# mavroOBD.net
KiCad netlist of a schematic drawn in EAGLE
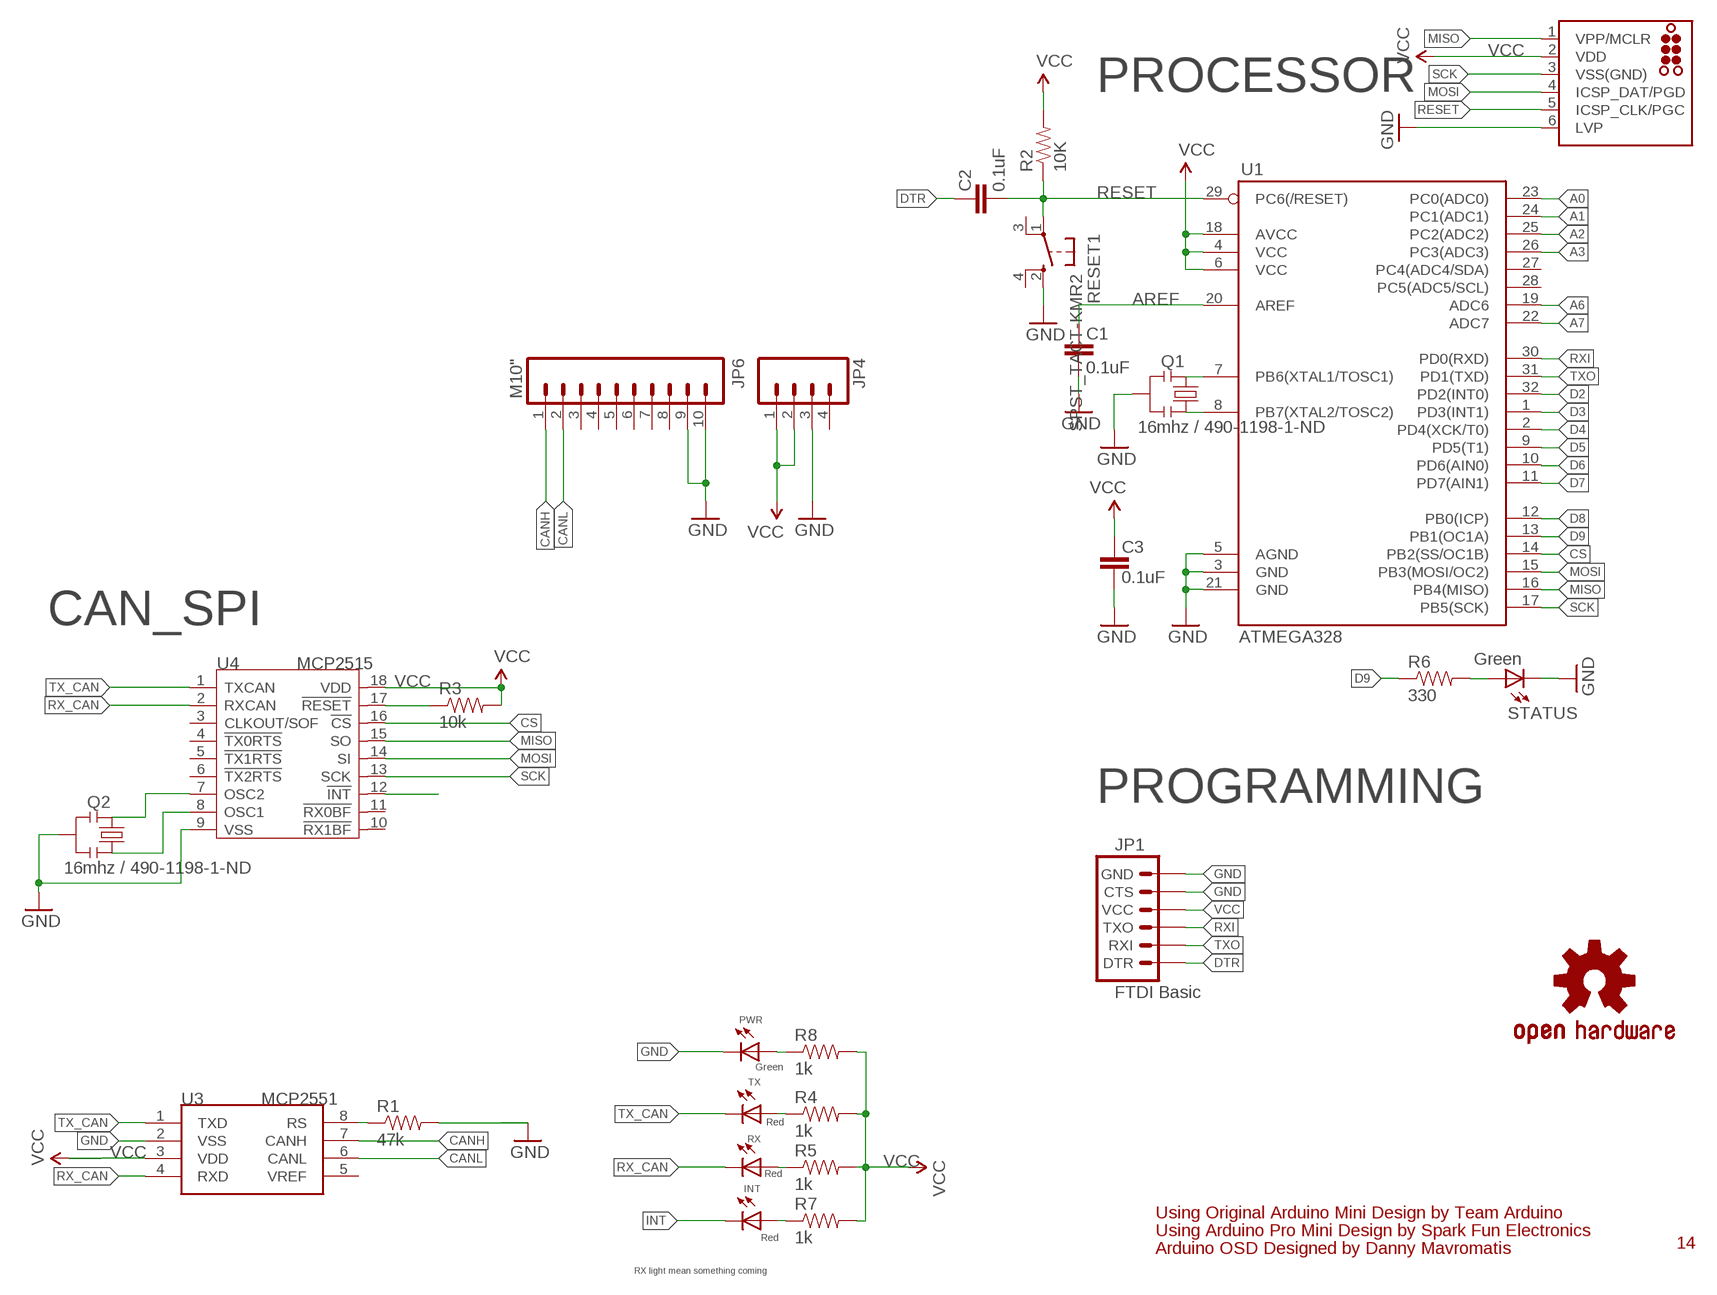
[diagram p0: schematic, sheet 1]

(export (version "E")
  (design (tool "Eeschema 10.0.6"))
  (components
    (comp (ref "C1")
      (value "0.1uF")
      (footprint "eagle-import:0603-CAP")
      (libsource (lib "eagle-import") (part "CAP0603-CAP"))
    )
    (comp (ref "C2")
      (value "0.1uF")
      (footprint "eagle-import:0603-CAP")
      (libsource (lib "eagle-import") (part "CAP0603-CAP"))
    )
    (comp (ref "C3")
      (value "0.1uF")
      (footprint "eagle-import:0603-CAP")
      (libsource (lib "eagle-import") (part "CAP0603-CAP"))
    )
    (comp (ref "INT")
      (value "Red")
      (footprint "eagle-import:0603-LED-ALT1")
      (libsource (lib "eagle-import") (part "LED"))
    )
    (comp (ref "J1")
      (value "TC2030-MCP-NL")
      (footprint "eagle-import:TC2030-MCP-NL")
      (libsource (lib "eagle-import") (part "TC2030-MCP-NL"))
    )
    (comp (ref "JP1")
      (value "FTDI Basic")
      (footprint "eagle-import:1X06")
      (libsource (lib "eagle-import") (part "ARDUINO_SERIAL_PROGRAMPTH"))
    )
    (comp (ref "JP4")
      (value "M04PTH")
      (footprint "eagle-import:1X04")
      (libsource (lib "eagle-import") (part "M04PTH"))
    )
    (comp (ref "JP6")
      (value "M10\"")
      (footprint "eagle-import:1X10")
      (libsource (lib "eagle-import") (part "M10{dblquote}"))
    )
    (comp (ref "PWR")
      (value "Green")
      (footprint "eagle-import:0603-LED-ALT1")
      (libsource (lib "eagle-import") (part "LED"))
    )
    (comp (ref "Q1")
      (value "16mhz / 490-1198-1-ND")
      (footprint "eagle-import:RESONATOR-SMD-1_1")
      (libsource (lib "eagle-import") (part "RESONATOR1{colon}1"))
    )
    (comp (ref "Q2")
      (value "16mhz / 490-1198-1-ND")
      (footprint "eagle-import:RESONATOR-SMD-1_1")
      (libsource (lib "eagle-import") (part "RESONATOR1{colon}1"))
    )
    (comp (ref "R1")
      (value "47k")
      (footprint "eagle-import:0603-RES")
      (libsource (lib "eagle-import") (part "SparkFun-Passives_RESISTOR0603-RES"))
    )
    (comp (ref "R2")
      (value "10K")
      (footprint "eagle-import:0603-RES")
      (libsource (lib "eagle-import") (part "RESISTOR0603-RES"))
    )
    (comp (ref "R3")
      (value "10k")
      (footprint "eagle-import:0603-RES")
      (libsource (lib "eagle-import") (part "SparkFun-Passives_RESISTOR0603-RES"))
    )
    (comp (ref "R4")
      (value "1k")
      (footprint "eagle-import:0603-RES")
      (libsource (lib "eagle-import") (part "SparkFun-Passives_RESISTOR0603-RES"))
    )
    (comp (ref "R5")
      (value "1k")
      (footprint "eagle-import:0603-RES")
      (libsource (lib "eagle-import") (part "SparkFun-Passives_RESISTOR0603-RES"))
    )
    (comp (ref "R6")
      (value "330")
      (footprint "eagle-import:0603-RES")
      (libsource (lib "eagle-import") (part "RESISTOR0603-RES"))
    )
    (comp (ref "R7")
      (value "1k")
      (footprint "eagle-import:0603-RES")
      (libsource (lib "eagle-import") (part "SparkFun-Passives_RESISTOR0603-RES"))
    )
    (comp (ref "R8")
      (value "1k")
      (footprint "eagle-import:0603-RES")
      (libsource (lib "eagle-import") (part "SparkFun-Passives_RESISTOR0603-RES"))
    )
    (comp (ref "RESET1")
      (value "SPST_TACT-KMR2")
      (footprint "eagle-import:KMR2")
      (libsource (lib "eagle-import") (part "SPST_TACT-KMR2"))
    )
    (comp (ref "RX")
      (value "Red")
      (footprint "eagle-import:0603-LED-ALT1")
      (libsource (lib "eagle-import") (part "LED"))
    )
    (comp (ref "STATUS")
      (value "Green")
      (footprint "eagle-import:0603-LED-ALT1")
      (libsource (lib "eagle-import") (part "LED"))
    )
    (comp (ref "TX")
      (value "Red")
      (footprint "eagle-import:0603-LED-ALT1")
      (libsource (lib "eagle-import") (part "LED"))
    )
    (comp (ref "U$3")
      (value "OSHW-LOGOS")
      (footprint "eagle-import:OSHW-LOGO-S")
      (libsource (lib "eagle-import") (part "OSHW-LOGOS"))
    )
    (comp (ref "U1")
      (value "ATMEGA328")
      (footprint "eagle-import:TQFP32-08")
      (libsource (lib "eagle-import") (part "ATMEGA168"))
    )
    (comp (ref "U3")
      (value "MCP2551")
      (footprint "eagle-import:SOIC8-6.0")
      (libsource (lib "eagle-import") (part "MCP2551-SOIC8"))
    )
    (comp (ref "U4")
      (value "MCP2515")
      (footprint "eagle-import:SOIC18")
      (libsource (lib "eagle-import") (part "MCP2515-SOIC18"))
    )
  )
  (nets
    (net (code "1") (name "/AREF") (class "Default")
      (node (ref "C1") (pin "2") (pinfunction "2_2") (pintype "passive"))
      (node (ref "U1") (pin "20") (pinfunction "AREF_20") (pintype "bidirectional"))
    )
    (net (code "2") (name "A0") (class "Default")
      (node (ref "U1") (pin "23") (pinfunction "PC0(ADC0)_23") (pintype "bidirectional"))
    )
    (net (code "3") (name "A1") (class "Default")
      (node (ref "U1") (pin "24") (pinfunction "PC1(ADC1)_24") (pintype "bidirectional"))
    )
    (net (code "4") (name "A2") (class "Default")
      (node (ref "U1") (pin "25") (pinfunction "PC2(ADC2)_25") (pintype "bidirectional"))
    )
    (net (code "5") (name "A3") (class "Default")
      (node (ref "U1") (pin "26") (pinfunction "PC3(ADC3)_26") (pintype "bidirectional"))
    )
    (net (code "6") (name "A6") (class "Default")
      (node (ref "U1") (pin "19") (pinfunction "ADC6_19") (pintype "bidirectional"))
    )
    (net (code "7") (name "A7") (class "Default")
      (node (ref "U1") (pin "22") (pinfunction "ADC7_22") (pintype "bidirectional"))
    )
    (net (code "8") (name "CANH") (class "Default")
      (node (ref "JP6") (pin "1") (pinfunction "1_1") (pintype "passive"))
      (node (ref "U3") (pin "7") (pinfunction "CANH_7") (pintype "bidirectional"))
    )
    (net (code "9") (name "CANL") (class "Default")
      (node (ref "JP6") (pin "2") (pinfunction "2_2") (pintype "passive"))
      (node (ref "U3") (pin "6") (pinfunction "CANL_6") (pintype "bidirectional"))
    )
    (net (code "10") (name "CS") (class "Default")
      (node (ref "U1") (pin "14") (pinfunction "PB2(SS/OC1B)_14") (pintype "bidirectional"))
      (node (ref "U4") (pin "16") (pinfunction "~{CS}_16") (pintype "input"))
    )
    (net (code "11") (name "D2") (class "Default")
      (node (ref "U1") (pin "32") (pinfunction "PD2(INT0)_32") (pintype "bidirectional"))
    )
    (net (code "12") (name "D3") (class "Default")
      (node (ref "U1") (pin "1") (pinfunction "PD3(INT1)_1") (pintype "bidirectional"))
    )
    (net (code "13") (name "D4") (class "Default")
      (node (ref "U1") (pin "2") (pinfunction "PD4(XCK/T0)_2") (pintype "bidirectional"))
    )
    (net (code "14") (name "D5") (class "Default")
      (node (ref "U1") (pin "9") (pinfunction "PD5(T1)_9") (pintype "bidirectional"))
    )
    (net (code "15") (name "D6") (class "Default")
      (node (ref "U1") (pin "10") (pinfunction "PD6(AIN0)_10") (pintype "bidirectional"))
    )
    (net (code "16") (name "D7") (class "Default")
      (node (ref "U1") (pin "11") (pinfunction "PD7(AIN1)_11") (pintype "bidirectional"))
    )
    (net (code "17") (name "D8") (class "Default")
      (node (ref "U1") (pin "12") (pinfunction "PB0(ICP)_12") (pintype "bidirectional"))
    )
    (net (code "18") (name "D9") (class "Default")
      (node (ref "R6") (pin "1") (pinfunction "1_1") (pintype "passive"))
      (node (ref "U1") (pin "13") (pinfunction "PB1(OC1A)_13") (pintype "bidirectional"))
    )
    (net (code "19") (name "DTR") (class "Default")
      (node (ref "C2") (pin "2") (pinfunction "2_2") (pintype "passive"))
      (node (ref "JP1") (pin "1") (pinfunction "DTR_1") (pintype "passive"))
    )
    (net (code "20") (name "GND") (class "Default")
      (node (ref "C1") (pin "1") (pinfunction "1_1") (pintype "passive"))
      (node (ref "C3") (pin "1") (pinfunction "1_1") (pintype "passive"))
      (node (ref "J1") (pin "6") (pinfunction "LVP_6") (pintype "bidirectional"))
      (node (ref "JP1") (pin "5") (pinfunction "CTS_5") (pintype "passive"))
      (node (ref "JP1") (pin "6") (pinfunction "GND_6") (pintype "passive"))
      (node (ref "JP4") (pin "3") (pinfunction "3_3") (pintype "passive"))
      (node (ref "JP6") (pin "10") (pinfunction "10_10") (pintype "passive"))
      (node (ref "JP6") (pin "9") (pinfunction "9_9") (pintype "passive"))
      (node (ref "PWR") (pin "C") (pinfunction "C_C") (pintype "passive"))
      (node (ref "Q1") (pin "2") (pinfunction "2_2") (pintype "passive"))
      (node (ref "Q2") (pin "2") (pinfunction "2_2") (pintype "passive"))
      (node (ref "R1") (pin "2") (pinfunction "2_2") (pintype "passive"))
      (node (ref "RESET1") (pin "2") (pinfunction "S_2") (pintype "passive"))
      (node (ref "STATUS") (pin "C") (pinfunction "C_C") (pintype "passive"))
      (node (ref "U1") (pin "21") (pinfunction "GND_21") (pintype "bidirectional"))
      (node (ref "U1") (pin "3") (pinfunction "GND_3") (pintype "bidirectional"))
      (node (ref "U1") (pin "5") (pinfunction "AGND_5") (pintype "bidirectional"))
      (node (ref "U3") (pin "2") (pinfunction "VSS_2") (pintype "bidirectional"))
      (node (ref "U4") (pin "9") (pinfunction "VSS_9") (pintype "power_in"))
    )
    (net (code "21") (name "INT") (class "Default")
      (node (ref "INT") (pin "C") (pinfunction "C_C") (pintype "passive"))
      (node (ref "U4") (pin "12") (pinfunction "~{INT}_12") (pintype "output"))
    )
    (net (code "22") (name "MISO") (class "Default")
      (node (ref "J1") (pin "1") (pinfunction "VPP/MCLR_1") (pintype "passive"))
      (node (ref "U1") (pin "16") (pinfunction "PB4(MISO)_16") (pintype "bidirectional"))
      (node (ref "U4") (pin "15") (pinfunction "SO_15") (pintype "output"))
    )
    (net (code "23") (name "MOSI") (class "Default")
      (node (ref "J1") (pin "4") (pinfunction "ICSP_DAT/PGD_4") (pintype "bidirectional"))
      (node (ref "U1") (pin "15") (pinfunction "PB3(MOSI/OC2)_15") (pintype "bidirectional"))
      (node (ref "U4") (pin "14") (pinfunction "SI_14") (pintype "input"))
    )
    (net (code "24") (name "Net-(INT-PadA)") (class "Default")
      (node (ref "INT") (pin "A") (pinfunction "A_A") (pintype "passive"))
      (node (ref "R7") (pin "1") (pinfunction "1_1") (pintype "passive"))
    )
    (net (code "25") (name "Net-(PWR-PadA)") (class "Default")
      (node (ref "PWR") (pin "A") (pinfunction "A_A") (pintype "passive"))
      (node (ref "R8") (pin "1") (pinfunction "1_1") (pintype "passive"))
    )
    (net (code "26") (name "Net-(R4-Pad1)") (class "Default")
      (node (ref "R4") (pin "1") (pinfunction "1_1") (pintype "passive"))
      (node (ref "TX") (pin "A") (pinfunction "A_A") (pintype "passive"))
    )
    (net (code "27") (name "Net-(R5-Pad1)") (class "Default")
      (node (ref "R5") (pin "1") (pinfunction "1_1") (pintype "passive"))
      (node (ref "RX") (pin "A") (pinfunction "A_A") (pintype "passive"))
    )
    (net (code "28") (name "Net-(R6-Pad2)") (class "Default")
      (node (ref "R6") (pin "2") (pinfunction "2_2") (pintype "passive"))
      (node (ref "STATUS") (pin "A") (pinfunction "A_A") (pintype "passive"))
    )
    (net (code "29") (name "Net-(U1-PB6(XTAL1{slash}TOSC1))") (class "Default")
      (node (ref "Q1") (pin "1") (pinfunction "1_1") (pintype "passive"))
      (node (ref "U1") (pin "7") (pinfunction "PB6(XTAL1/TOSC1)_7") (pintype "bidirectional"))
    )
    (net (code "30") (name "Net-(U1-PB7(XTAL2{slash}TOSC2))") (class "Default")
      (node (ref "Q1") (pin "3") (pinfunction "3_3") (pintype "passive"))
      (node (ref "U1") (pin "8") (pinfunction "PB7(XTAL2/TOSC2)_8") (pintype "bidirectional"))
    )
    (net (code "31") (name "Net-(U3-RS)") (class "Default")
      (node (ref "R1") (pin "1") (pinfunction "1_1") (pintype "passive"))
      (node (ref "U3") (pin "8") (pinfunction "RS_8") (pintype "bidirectional"))
    )
    (net (code "32") (name "Net-(U4-OSC1)") (class "Default")
      (node (ref "Q2") (pin "3") (pinfunction "3_3") (pintype "passive"))
      (node (ref "U4") (pin "8") (pinfunction "OSC1_8") (pintype "input"))
    )
    (net (code "33") (name "Net-(U4-OSC2)") (class "Default")
      (node (ref "Q2") (pin "1") (pinfunction "1_1") (pintype "passive"))
      (node (ref "U4") (pin "7") (pinfunction "OSC2_7") (pintype "output"))
    )
    (net (code "34") (name "Net-(U4-~{RESET})") (class "Default")
      (node (ref "R3") (pin "1") (pinfunction "1_1") (pintype "passive"))
      (node (ref "U4") (pin "17") (pinfunction "~{RESET}_17") (pintype "input"))
    )
    (net (code "35") (name "RESET") (class "Default")
      (node (ref "C2") (pin "1") (pinfunction "1_1") (pintype "passive"))
      (node (ref "J1") (pin "5") (pinfunction "ICSP_CLK/PGC_5") (pintype "output"))
      (node (ref "R2") (pin "1") (pinfunction "1_1") (pintype "passive"))
      (node (ref "RESET1") (pin "1") (pinfunction "P_1") (pintype "passive"))
      (node (ref "U1") (pin "29") (pinfunction "PC6(/RESET)_29") (pintype "bidirectional"))
    )
    (net (code "36") (name "RXI") (class "Default")
      (node (ref "JP1") (pin "3") (pinfunction "TXO_3") (pintype "passive"))
      (node (ref "U1") (pin "30") (pinfunction "PD0(RXD)_30") (pintype "bidirectional"))
    )
    (net (code "37") (name "RX_CAN") (class "Default")
      (node (ref "RX") (pin "C") (pinfunction "C_C") (pintype "passive"))
      (node (ref "U3") (pin "4") (pinfunction "RXD_4") (pintype "bidirectional"))
      (node (ref "U4") (pin "2") (pinfunction "RXCAN_2") (pintype "input"))
    )
    (net (code "38") (name "SCK") (class "Default")
      (node (ref "J1") (pin "3") (pinfunction "VSS(GND)_3") (pintype "power_in"))
      (node (ref "U1") (pin "17") (pinfunction "PB5(SCK)_17") (pintype "bidirectional"))
      (node (ref "U4") (pin "13") (pinfunction "SCK_13") (pintype "input"))
    )
    (net (code "39") (name "TXO") (class "Default")
      (node (ref "JP1") (pin "2") (pinfunction "RXI_2") (pintype "passive"))
      (node (ref "U1") (pin "31") (pinfunction "PD1(TXD)_31") (pintype "bidirectional"))
    )
    (net (code "40") (name "TX_CAN") (class "Default")
      (node (ref "TX") (pin "C") (pinfunction "C_C") (pintype "passive"))
      (node (ref "U3") (pin "1") (pinfunction "TXD_1") (pintype "bidirectional"))
      (node (ref "U4") (pin "1") (pinfunction "TXCAN_1") (pintype "output"))
    )
    (net (code "41") (name "VCC") (class "Default")
      (node (ref "C3") (pin "2") (pinfunction "2_2") (pintype "passive"))
      (node (ref "J1") (pin "2") (pinfunction "VDD_2") (pintype "power_in"))
      (node (ref "JP1") (pin "4") (pinfunction "VCC_4") (pintype "passive"))
      (node (ref "JP4") (pin "1") (pinfunction "1_1") (pintype "passive"))
      (node (ref "JP4") (pin "2") (pinfunction "2_2") (pintype "passive"))
      (node (ref "R2") (pin "2") (pinfunction "2_2") (pintype "passive"))
      (node (ref "R3") (pin "2") (pinfunction "2_2") (pintype "passive"))
      (node (ref "R4") (pin "2") (pinfunction "2_2") (pintype "passive"))
      (node (ref "R5") (pin "2") (pinfunction "2_2") (pintype "passive"))
      (node (ref "R7") (pin "2") (pinfunction "2_2") (pintype "passive"))
      (node (ref "R8") (pin "2") (pinfunction "2_2") (pintype "passive"))
      (node (ref "U1") (pin "18") (pinfunction "AVCC_18") (pintype "bidirectional"))
      (node (ref "U1") (pin "4") (pinfunction "VCC_4") (pintype "bidirectional"))
      (node (ref "U1") (pin "6") (pinfunction "VCC_6") (pintype "bidirectional"))
      (node (ref "U3") (pin "3") (pinfunction "VDD_3") (pintype "bidirectional"))
      (node (ref "U4") (pin "18") (pinfunction "VDD_18") (pintype "power_in"))
    )
    (net (code "42") (name "unconnected-(JP4-Pad4)") (class "Default")
      (node (ref "JP4") (pin "4") (pinfunction "4_4") (pintype "passive"))
    )
    (net (code "43") (name "unconnected-(JP6-Pad3)") (class "Default")
      (node (ref "JP6") (pin "3") (pinfunction "3_3") (pintype "passive"))
    )
    (net (code "44") (name "unconnected-(JP6-Pad4)") (class "Default")
      (node (ref "JP6") (pin "4") (pinfunction "4_4") (pintype "passive"))
    )
    (net (code "45") (name "unconnected-(JP6-Pad5)") (class "Default")
      (node (ref "JP6") (pin "5") (pinfunction "5_5") (pintype "passive"))
    )
    (net (code "46") (name "unconnected-(JP6-Pad6)") (class "Default")
      (node (ref "JP6") (pin "6") (pinfunction "6_6") (pintype "passive"))
    )
    (net (code "47") (name "unconnected-(JP6-Pad7)") (class "Default")
      (node (ref "JP6") (pin "7") (pinfunction "7_7") (pintype "passive"))
    )
    (net (code "48") (name "unconnected-(JP6-Pad8)") (class "Default")
      (node (ref "JP6") (pin "8") (pinfunction "8_8") (pintype "passive"))
    )
    (net (code "49") (name "unconnected-(RESET1-P1-Pad3)") (class "Default")
      (node (ref "RESET1") (pin "3") (pinfunction "P1_3") (pintype "passive"))
    )
    (net (code "50") (name "unconnected-(RESET1-S1-Pad4)") (class "Default")
      (node (ref "RESET1") (pin "4") (pinfunction "S1_4") (pintype "passive"))
    )
    (net (code "51") (name "unconnected-(U1-PC4(ADC4{slash}SDA)-Pad27)") (class "Default")
      (node (ref "U1") (pin "27") (pinfunction "PC4(ADC4/SDA)_27") (pintype "bidirectional"))
    )
    (net (code "52") (name "unconnected-(U1-PC5(ADC5{slash}SCL)-Pad28)") (class "Default")
      (node (ref "U1") (pin "28") (pinfunction "PC5(ADC5/SCL)_28") (pintype "bidirectional"))
    )
    (net (code "53") (name "unconnected-(U3-VREF-Pad5)") (class "Default")
      (node (ref "U3") (pin "5") (pinfunction "VREF_5") (pintype "bidirectional"))
    )
    (net (code "54") (name "unconnected-(U4-CLKOUT{slash}SOF-Pad3)") (class "Default")
      (node (ref "U4") (pin "3") (pinfunction "CLKOUT/SOF_3") (pintype "output"))
    )
    (net (code "55") (name "unconnected-(U4-~{RX0BF}-Pad11)") (class "Default")
      (node (ref "U4") (pin "11") (pinfunction "~{RX0BF}_11") (pintype "output"))
    )
    (net (code "56") (name "unconnected-(U4-~{RX1BF}-Pad10)") (class "Default")
      (node (ref "U4") (pin "10") (pinfunction "~{RX1BF}_10") (pintype "output"))
    )
    (net (code "57") (name "unconnected-(U4-~{TX0RTS}-Pad4)") (class "Default")
      (node (ref "U4") (pin "4") (pinfunction "~{TX0RTS}_4") (pintype "input"))
    )
    (net (code "58") (name "unconnected-(U4-~{TX1RTS}-Pad5)") (class "Default")
      (node (ref "U4") (pin "5") (pinfunction "~{TX1RTS}_5") (pintype "input"))
    )
    (net (code "59") (name "unconnected-(U4-~{TX2RTS}-Pad6)") (class "Default")
      (node (ref "U4") (pin "6") (pinfunction "~{TX2RTS}_6") (pintype "input"))
    )
  )
)
